# m1-instruction-register.net
KiCad netlist of a schematic drawn in EAGLE
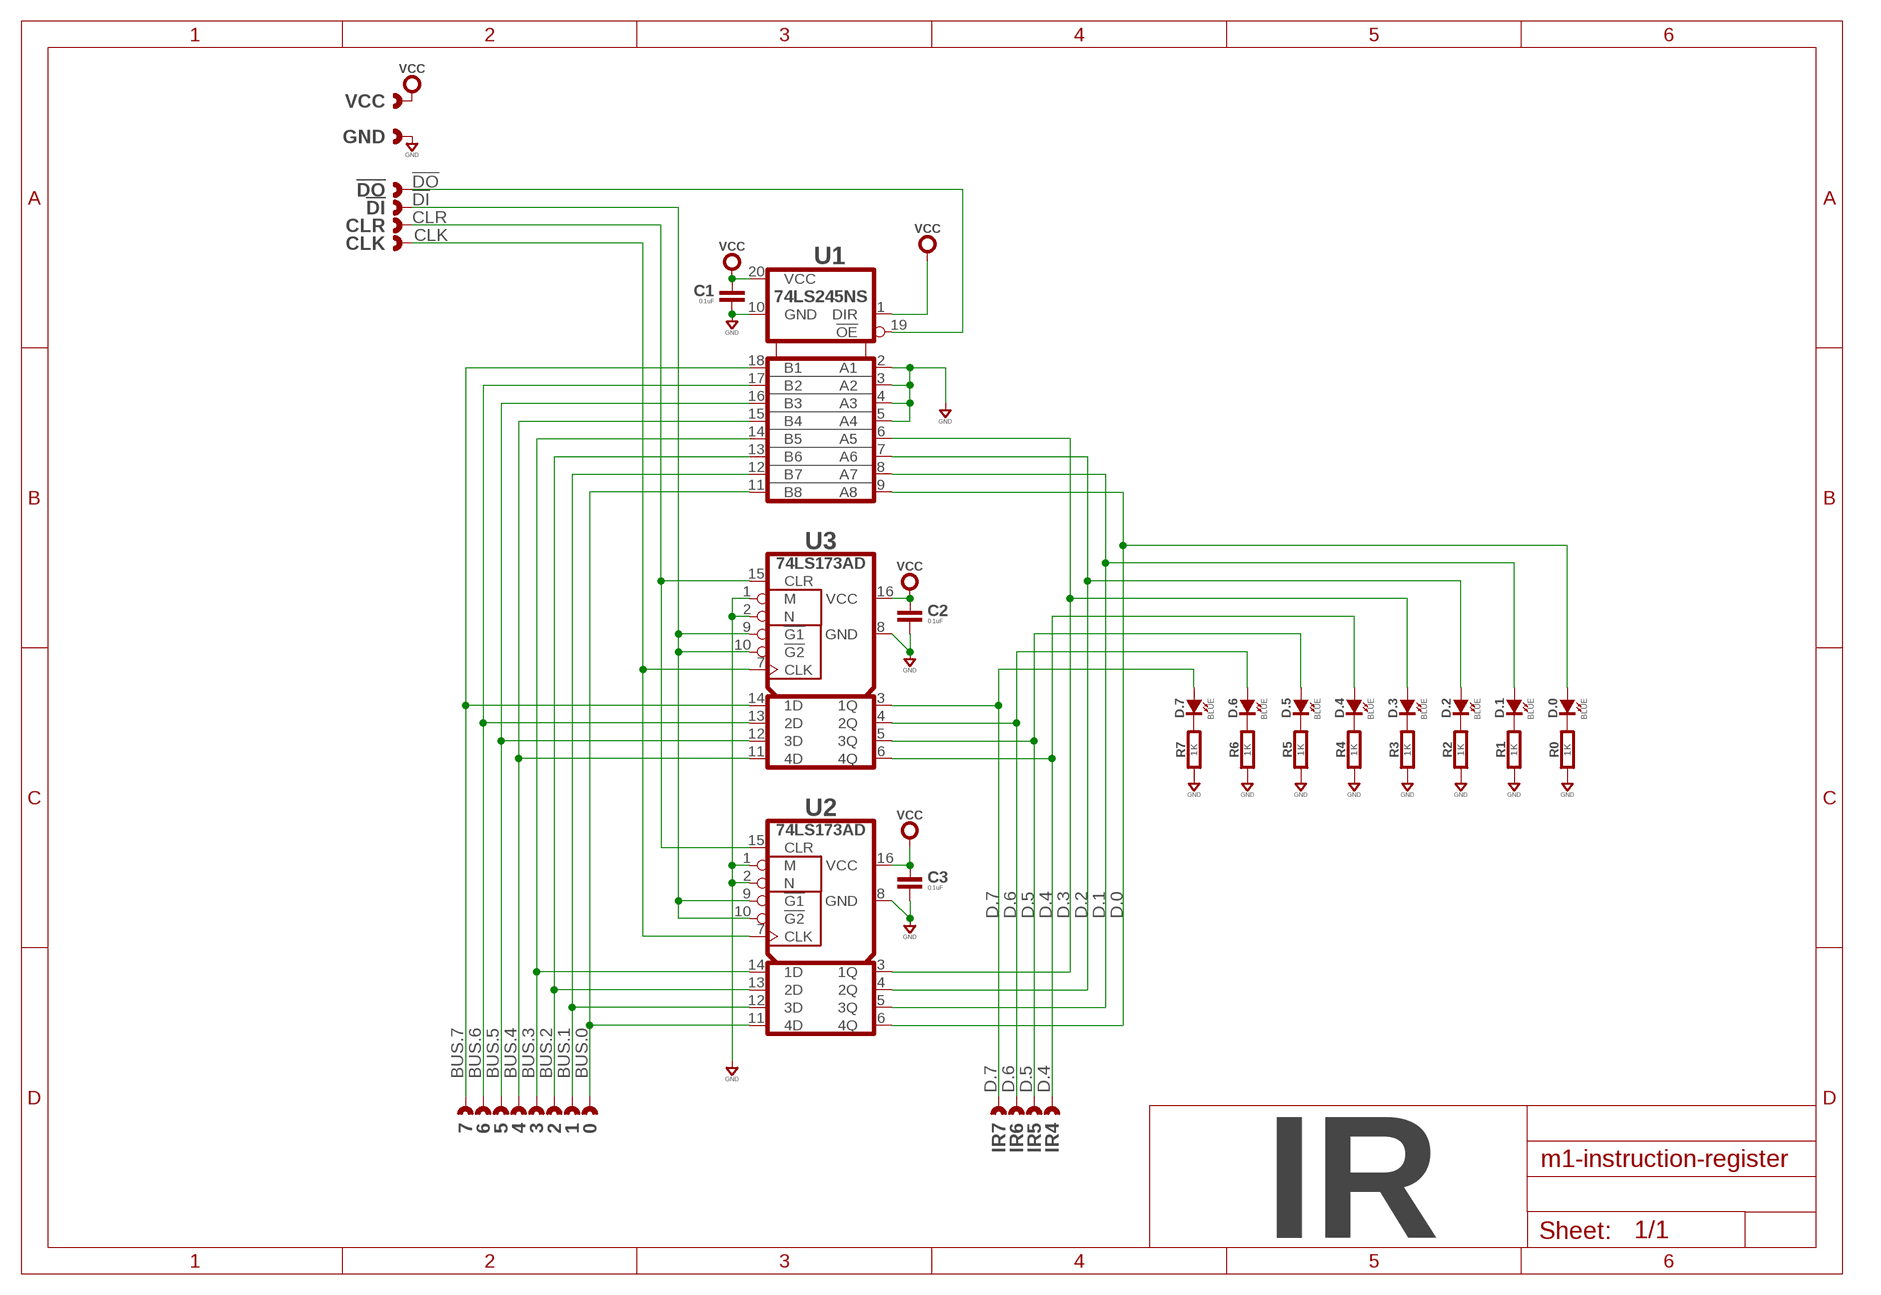
[diagram p0: schematic, sheet 1]

(export (version "E")
  (design (tool "Eeschema 10.0.6"))
  (components
    (comp (ref "!DI")
      (value "CAST-01X1")
      (footprint "eagle-import:CAST01-2.54MM")
      (libsource (lib "eagle-import") (part "CAST-01X1"))
    )
    (comp (ref "!DO")
      (value "CAST-01X1")
      (footprint "eagle-import:CAST01-2.54MM")
      (libsource (lib "eagle-import") (part "CAST-01X1"))
    )
    (comp (ref "0")
      (value "CAST-01X1")
      (footprint "eagle-import:CAST01-2.54MM")
      (libsource (lib "eagle-import") (part "CAST-01X1"))
    )
    (comp (ref "1")
      (value "CAST-01X1")
      (footprint "eagle-import:CAST01-2.54MM")
      (libsource (lib "eagle-import") (part "CAST-01X1"))
    )
    (comp (ref "2")
      (value "CAST-01X1")
      (footprint "eagle-import:CAST01-2.54MM")
      (libsource (lib "eagle-import") (part "CAST-01X1"))
    )
    (comp (ref "3")
      (value "CAST-01X1")
      (footprint "eagle-import:CAST01-2.54MM")
      (libsource (lib "eagle-import") (part "CAST-01X1"))
    )
    (comp (ref "4")
      (value "CAST-01X1")
      (footprint "eagle-import:CAST01-2.54MM")
      (libsource (lib "eagle-import") (part "CAST-01X1"))
    )
    (comp (ref "5")
      (value "CAST-01X1")
      (footprint "eagle-import:CAST01-2.54MM")
      (libsource (lib "eagle-import") (part "CAST-01X1"))
    )
    (comp (ref "6")
      (value "CAST-01X1")
      (footprint "eagle-import:CAST01-2.54MM")
      (libsource (lib "eagle-import") (part "CAST-01X1"))
    )
    (comp (ref "7")
      (value "CAST-01X1")
      (footprint "eagle-import:CAST01-2.54MM")
      (libsource (lib "eagle-import") (part "CAST-01X1"))
    )
    (comp (ref "C1")
      (value "0.1uF")
      (footprint "eagle-import:0603-CAP")
      (libsource (lib "eagle-import") (part "CAPACITOR0603"))
    )
    (comp (ref "C2")
      (value "0.1uF")
      (footprint "eagle-import:0603-CAP")
      (libsource (lib "eagle-import") (part "CAPACITOR0603"))
    )
    (comp (ref "C3")
      (value "0.1uF")
      (footprint "eagle-import:0603-CAP")
      (libsource (lib "eagle-import") (part "CAPACITOR0603"))
    )
    (comp (ref "CLK")
      (value "CAST-01X1")
      (footprint "eagle-import:CAST01-2.54MM")
      (libsource (lib "eagle-import") (part "CAST-01X1"))
    )
    (comp (ref "CLR")
      (value "CAST-01X1")
      (footprint "eagle-import:CAST01-2.54MM")
      (libsource (lib "eagle-import") (part "CAST-01X1"))
    )
    (comp (ref "D.0")
      (value "BLUE")
      (footprint "eagle-import:SMD_0603")
      (libsource (lib "eagle-import") (part "SMT0603"))
    )
    (comp (ref "D.1")
      (value "BLUE")
      (footprint "eagle-import:SMD_0603")
      (libsource (lib "eagle-import") (part "SMT0603"))
    )
    (comp (ref "D.2")
      (value "BLUE")
      (footprint "eagle-import:SMD_0603")
      (libsource (lib "eagle-import") (part "SMT0603"))
    )
    (comp (ref "D.3")
      (value "BLUE")
      (footprint "eagle-import:SMD_0603")
      (libsource (lib "eagle-import") (part "SMT0603"))
    )
    (comp (ref "D.4")
      (value "BLUE")
      (footprint "eagle-import:SMD_0603")
      (libsource (lib "eagle-import") (part "SMT0603"))
    )
    (comp (ref "D.5")
      (value "BLUE")
      (footprint "eagle-import:SMD_0603")
      (libsource (lib "eagle-import") (part "SMT0603"))
    )
    (comp (ref "D.6")
      (value "BLUE")
      (footprint "eagle-import:SMD_0603")
      (libsource (lib "eagle-import") (part "SMT0603"))
    )
    (comp (ref "D.7")
      (value "BLUE")
      (footprint "eagle-import:SMD_0603")
      (libsource (lib "eagle-import") (part "SMT0603"))
    )
    (comp (ref "GND")
      (value "CAST-01X1")
      (footprint "eagle-import:CAST01-2.54MM")
      (libsource (lib "eagle-import") (part "CAST-01X1"))
    )
    (comp (ref "IR4")
      (value "CAST-01X1")
      (footprint "eagle-import:CAST01-2.54MM")
      (libsource (lib "eagle-import") (part "CAST-01X1"))
    )
    (comp (ref "IR5")
      (value "CAST-01X1")
      (footprint "eagle-import:CAST01-2.54MM")
      (libsource (lib "eagle-import") (part "CAST-01X1"))
    )
    (comp (ref "IR6")
      (value "CAST-01X1")
      (footprint "eagle-import:CAST01-2.54MM")
      (libsource (lib "eagle-import") (part "CAST-01X1"))
    )
    (comp (ref "IR7")
      (value "CAST-01X1")
      (footprint "eagle-import:CAST01-2.54MM")
      (libsource (lib "eagle-import") (part "CAST-01X1"))
    )
    (comp (ref "R0")
      (value "1K")
      (footprint "eagle-import:0603-RES")
      (libsource (lib "eagle-import") (part "RESISTOR0603"))
    )
    (comp (ref "R1")
      (value "1K")
      (footprint "eagle-import:0603-RES")
      (libsource (lib "eagle-import") (part "RESISTOR0603"))
    )
    (comp (ref "R2")
      (value "1K")
      (footprint "eagle-import:0603-RES")
      (libsource (lib "eagle-import") (part "RESISTOR0603"))
    )
    (comp (ref "R3")
      (value "1K")
      (footprint "eagle-import:0603-RES")
      (libsource (lib "eagle-import") (part "RESISTOR0603"))
    )
    (comp (ref "R4")
      (value "1K")
      (footprint "eagle-import:0603-RES")
      (libsource (lib "eagle-import") (part "RESISTOR0603"))
    )
    (comp (ref "R5")
      (value "1K")
      (footprint "eagle-import:0603-RES")
      (libsource (lib "eagle-import") (part "RESISTOR0603"))
    )
    (comp (ref "R6")
      (value "1K")
      (footprint "eagle-import:0603-RES")
      (libsource (lib "eagle-import") (part "RESISTOR0603"))
    )
    (comp (ref "R7")
      (value "1K")
      (footprint "eagle-import:0603-RES")
      (libsource (lib "eagle-import") (part "RESISTOR0603"))
    )
    (comp (ref "U1")
      (value "74LS245NS")
      (footprint "eagle-import:SO20")
      (libsource (lib "eagle-import") (part "74245?NSLS"))
    )
    (comp (ref "U2")
      (value "74LS173AD")
      (footprint "eagle-import:SO16")
      (libsource (lib "eagle-import") (part "74173A?DLS"))
    )
    (comp (ref "U3")
      (value "74LS173AD")
      (footprint "eagle-import:SO16")
      (libsource (lib "eagle-import") (part "74173A?DLS"))
    )
    (comp (ref "VCC")
      (value "CAST-01X1")
      (footprint "eagle-import:CAST01-2.54MM")
      (libsource (lib "eagle-import") (part "CAST-01X1"))
    )
  )
  (nets
    (net (code "1") (name "/BUS.0") (class "Default")
      (node (ref "0") (pin "1") (pinfunction "1_1") (pintype "bidirectional"))
      (node (ref "U1") (pin "11") (pinfunction "B8_11") (pintype "bidirectional"))
      (node (ref "U2") (pin "11") (pinfunction "4D_11") (pintype "bidirectional"))
    )
    (net (code "2") (name "/BUS.1") (class "Default")
      (node (ref "1") (pin "1") (pinfunction "1_1") (pintype "bidirectional"))
      (node (ref "U1") (pin "12") (pinfunction "B7_12") (pintype "bidirectional"))
      (node (ref "U2") (pin "12") (pinfunction "3D_12") (pintype "bidirectional"))
    )
    (net (code "3") (name "/BUS.2") (class "Default")
      (node (ref "2") (pin "1") (pinfunction "1_1") (pintype "bidirectional"))
      (node (ref "U1") (pin "13") (pinfunction "B6_13") (pintype "bidirectional"))
      (node (ref "U2") (pin "13") (pinfunction "2D_13") (pintype "bidirectional"))
    )
    (net (code "4") (name "/BUS.3") (class "Default")
      (node (ref "3") (pin "1") (pinfunction "1_1") (pintype "bidirectional"))
      (node (ref "U1") (pin "14") (pinfunction "B5_14") (pintype "bidirectional"))
      (node (ref "U2") (pin "14") (pinfunction "1D_14") (pintype "bidirectional"))
    )
    (net (code "5") (name "/BUS.4") (class "Default")
      (node (ref "4") (pin "1") (pinfunction "1_1") (pintype "bidirectional"))
      (node (ref "U1") (pin "15") (pinfunction "B4_15") (pintype "bidirectional"))
      (node (ref "U3") (pin "11") (pinfunction "4D_11") (pintype "bidirectional"))
    )
    (net (code "6") (name "/BUS.5") (class "Default")
      (node (ref "5") (pin "1") (pinfunction "1_1") (pintype "bidirectional"))
      (node (ref "U1") (pin "16") (pinfunction "B3_16") (pintype "bidirectional"))
      (node (ref "U3") (pin "12") (pinfunction "3D_12") (pintype "bidirectional"))
    )
    (net (code "7") (name "/BUS.6") (class "Default")
      (node (ref "6") (pin "1") (pinfunction "1_1") (pintype "bidirectional"))
      (node (ref "U1") (pin "17") (pinfunction "B2_17") (pintype "bidirectional"))
      (node (ref "U3") (pin "13") (pinfunction "2D_13") (pintype "bidirectional"))
    )
    (net (code "8") (name "/BUS.7") (class "Default")
      (node (ref "7") (pin "1") (pinfunction "1_1") (pintype "bidirectional"))
      (node (ref "U1") (pin "18") (pinfunction "B1_18") (pintype "bidirectional"))
      (node (ref "U3") (pin "14") (pinfunction "1D_14") (pintype "bidirectional"))
    )
    (net (code "9") (name "/CLK") (class "Default")
      (node (ref "CLK") (pin "1") (pinfunction "1_1") (pintype "bidirectional"))
      (node (ref "U2") (pin "7") (pinfunction "CLK_7") (pintype "bidirectional"))
      (node (ref "U3") (pin "7") (pinfunction "CLK_7") (pintype "bidirectional"))
    )
    (net (code "10") (name "/CLR") (class "Default")
      (node (ref "CLR") (pin "1") (pinfunction "1_1") (pintype "bidirectional"))
      (node (ref "U2") (pin "15") (pinfunction "CLR_15") (pintype "bidirectional"))
      (node (ref "U3") (pin "15") (pinfunction "CLR_15") (pintype "bidirectional"))
    )
    (net (code "11") (name "/D.0") (class "Default")
      (node (ref "D.0") (pin "A") (pinfunction "A_A") (pintype "passive"))
      (node (ref "U1") (pin "9") (pinfunction "A8_9") (pintype "bidirectional"))
      (node (ref "U2") (pin "6") (pinfunction "4Q_6") (pintype "bidirectional"))
    )
    (net (code "12") (name "/D.1") (class "Default")
      (node (ref "D.1") (pin "A") (pinfunction "A_A") (pintype "passive"))
      (node (ref "U1") (pin "8") (pinfunction "A7_8") (pintype "bidirectional"))
      (node (ref "U2") (pin "5") (pinfunction "3Q_5") (pintype "bidirectional"))
    )
    (net (code "13") (name "/D.2") (class "Default")
      (node (ref "D.2") (pin "A") (pinfunction "A_A") (pintype "passive"))
      (node (ref "U1") (pin "7") (pinfunction "A6_7") (pintype "bidirectional"))
      (node (ref "U2") (pin "4") (pinfunction "2Q_4") (pintype "bidirectional"))
    )
    (net (code "14") (name "/D.3") (class "Default")
      (node (ref "D.3") (pin "A") (pinfunction "A_A") (pintype "passive"))
      (node (ref "U1") (pin "6") (pinfunction "A5_6") (pintype "bidirectional"))
      (node (ref "U2") (pin "3") (pinfunction "1Q_3") (pintype "bidirectional"))
    )
    (net (code "15") (name "/D.4") (class "Default")
      (node (ref "D.4") (pin "A") (pinfunction "A_A") (pintype "passive"))
      (node (ref "IR4") (pin "1") (pinfunction "1_1") (pintype "bidirectional"))
      (node (ref "U3") (pin "6") (pinfunction "4Q_6") (pintype "bidirectional"))
    )
    (net (code "16") (name "/D.5") (class "Default")
      (node (ref "D.5") (pin "A") (pinfunction "A_A") (pintype "passive"))
      (node (ref "IR5") (pin "1") (pinfunction "1_1") (pintype "bidirectional"))
      (node (ref "U3") (pin "5") (pinfunction "3Q_5") (pintype "bidirectional"))
    )
    (net (code "17") (name "/D.6") (class "Default")
      (node (ref "D.6") (pin "A") (pinfunction "A_A") (pintype "passive"))
      (node (ref "IR6") (pin "1") (pinfunction "1_1") (pintype "bidirectional"))
      (node (ref "U3") (pin "4") (pinfunction "2Q_4") (pintype "bidirectional"))
    )
    (net (code "18") (name "/D.7") (class "Default")
      (node (ref "D.7") (pin "A") (pinfunction "A_A") (pintype "passive"))
      (node (ref "IR7") (pin "1") (pinfunction "1_1") (pintype "bidirectional"))
      (node (ref "U3") (pin "3") (pinfunction "1Q_3") (pintype "bidirectional"))
    )
    (net (code "19") (name "/~{DI}") (class "Default")
      (node (ref "!DI") (pin "1") (pinfunction "1_1") (pintype "bidirectional"))
      (node (ref "U2") (pin "10") (pinfunction "~{G2}_10") (pintype "bidirectional"))
      (node (ref "U2") (pin "9") (pinfunction "~{G1}_9") (pintype "bidirectional"))
      (node (ref "U3") (pin "10") (pinfunction "~{G2}_10") (pintype "bidirectional"))
      (node (ref "U3") (pin "9") (pinfunction "~{G1}_9") (pintype "bidirectional"))
    )
    (net (code "20") (name "/~{DO}") (class "Default")
      (node (ref "!DO") (pin "1") (pinfunction "1_1") (pintype "bidirectional"))
      (node (ref "U1") (pin "19") (pinfunction "~{OE}_19") (pintype "bidirectional"))
    )
    (net (code "21") (name "GND") (class "Default")
      (node (ref "C1") (pin "2") (pinfunction "2_2") (pintype "passive"))
      (node (ref "C2") (pin "2") (pinfunction "2_2") (pintype "passive"))
      (node (ref "C3") (pin "2") (pinfunction "2_2") (pintype "passive"))
      (node (ref "GND") (pin "1") (pinfunction "1_1") (pintype "bidirectional"))
      (node (ref "R0") (pin "1") (pinfunction "1_1") (pintype "passive"))
      (node (ref "R1") (pin "1") (pinfunction "1_1") (pintype "passive"))
      (node (ref "R2") (pin "1") (pinfunction "1_1") (pintype "passive"))
      (node (ref "R3") (pin "1") (pinfunction "1_1") (pintype "passive"))
      (node (ref "R4") (pin "1") (pinfunction "1_1") (pintype "passive"))
      (node (ref "R5") (pin "1") (pinfunction "1_1") (pintype "passive"))
      (node (ref "R6") (pin "1") (pinfunction "1_1") (pintype "passive"))
      (node (ref "R7") (pin "1") (pinfunction "1_1") (pintype "passive"))
      (node (ref "U1") (pin "10") (pinfunction "GND_10") (pintype "bidirectional"))
      (node (ref "U1") (pin "2") (pinfunction "A1_2") (pintype "bidirectional"))
      (node (ref "U1") (pin "3") (pinfunction "A2_3") (pintype "bidirectional"))
      (node (ref "U1") (pin "4") (pinfunction "A3_4") (pintype "bidirectional"))
      (node (ref "U1") (pin "5") (pinfunction "A4_5") (pintype "bidirectional"))
      (node (ref "U2") (pin "1") (pinfunction "M_1") (pintype "bidirectional"))
      (node (ref "U2") (pin "2") (pinfunction "N_2") (pintype "bidirectional"))
      (node (ref "U2") (pin "8") (pinfunction "GND_8") (pintype "bidirectional"))
      (node (ref "U3") (pin "1") (pinfunction "M_1") (pintype "bidirectional"))
      (node (ref "U3") (pin "2") (pinfunction "N_2") (pintype "bidirectional"))
      (node (ref "U3") (pin "8") (pinfunction "GND_8") (pintype "bidirectional"))
    )
    (net (code "22") (name "Net-(D.0-C)") (class "Default")
      (node (ref "D.0") (pin "K") (pinfunction "C_K") (pintype "passive"))
      (node (ref "R0") (pin "2") (pinfunction "2_2") (pintype "passive"))
    )
    (net (code "23") (name "Net-(D.1-C)") (class "Default")
      (node (ref "D.1") (pin "K") (pinfunction "C_K") (pintype "passive"))
      (node (ref "R1") (pin "2") (pinfunction "2_2") (pintype "passive"))
    )
    (net (code "24") (name "Net-(D.2-C)") (class "Default")
      (node (ref "D.2") (pin "K") (pinfunction "C_K") (pintype "passive"))
      (node (ref "R2") (pin "2") (pinfunction "2_2") (pintype "passive"))
    )
    (net (code "25") (name "Net-(D.3-C)") (class "Default")
      (node (ref "D.3") (pin "K") (pinfunction "C_K") (pintype "passive"))
      (node (ref "R3") (pin "2") (pinfunction "2_2") (pintype "passive"))
    )
    (net (code "26") (name "Net-(D.4-C)") (class "Default")
      (node (ref "D.4") (pin "K") (pinfunction "C_K") (pintype "passive"))
      (node (ref "R4") (pin "2") (pinfunction "2_2") (pintype "passive"))
    )
    (net (code "27") (name "Net-(D.5-C)") (class "Default")
      (node (ref "D.5") (pin "K") (pinfunction "C_K") (pintype "passive"))
      (node (ref "R5") (pin "2") (pinfunction "2_2") (pintype "passive"))
    )
    (net (code "28") (name "Net-(D.6-C)") (class "Default")
      (node (ref "D.6") (pin "K") (pinfunction "C_K") (pintype "passive"))
      (node (ref "R6") (pin "2") (pinfunction "2_2") (pintype "passive"))
    )
    (net (code "29") (name "Net-(D.7-C)") (class "Default")
      (node (ref "D.7") (pin "K") (pinfunction "C_K") (pintype "passive"))
      (node (ref "R7") (pin "2") (pinfunction "2_2") (pintype "passive"))
    )
    (net (code "30") (name "VCC") (class "Default")
      (node (ref "C1") (pin "1") (pinfunction "1_1") (pintype "passive"))
      (node (ref "C2") (pin "1") (pinfunction "1_1") (pintype "passive"))
      (node (ref "C3") (pin "1") (pinfunction "1_1") (pintype "passive"))
      (node (ref "U1") (pin "1") (pinfunction "DIR_1") (pintype "bidirectional"))
      (node (ref "U1") (pin "20") (pinfunction "VCC_20") (pintype "bidirectional"))
      (node (ref "U2") (pin "16") (pinfunction "VCC_16") (pintype "bidirectional"))
      (node (ref "U3") (pin "16") (pinfunction "VCC_16") (pintype "bidirectional"))
      (node (ref "VCC") (pin "1") (pinfunction "1_1") (pintype "bidirectional"))
    )
  )
)
